# RSL10_Sch.net
KiCad netlist of a schematic drawn in Altium Designer
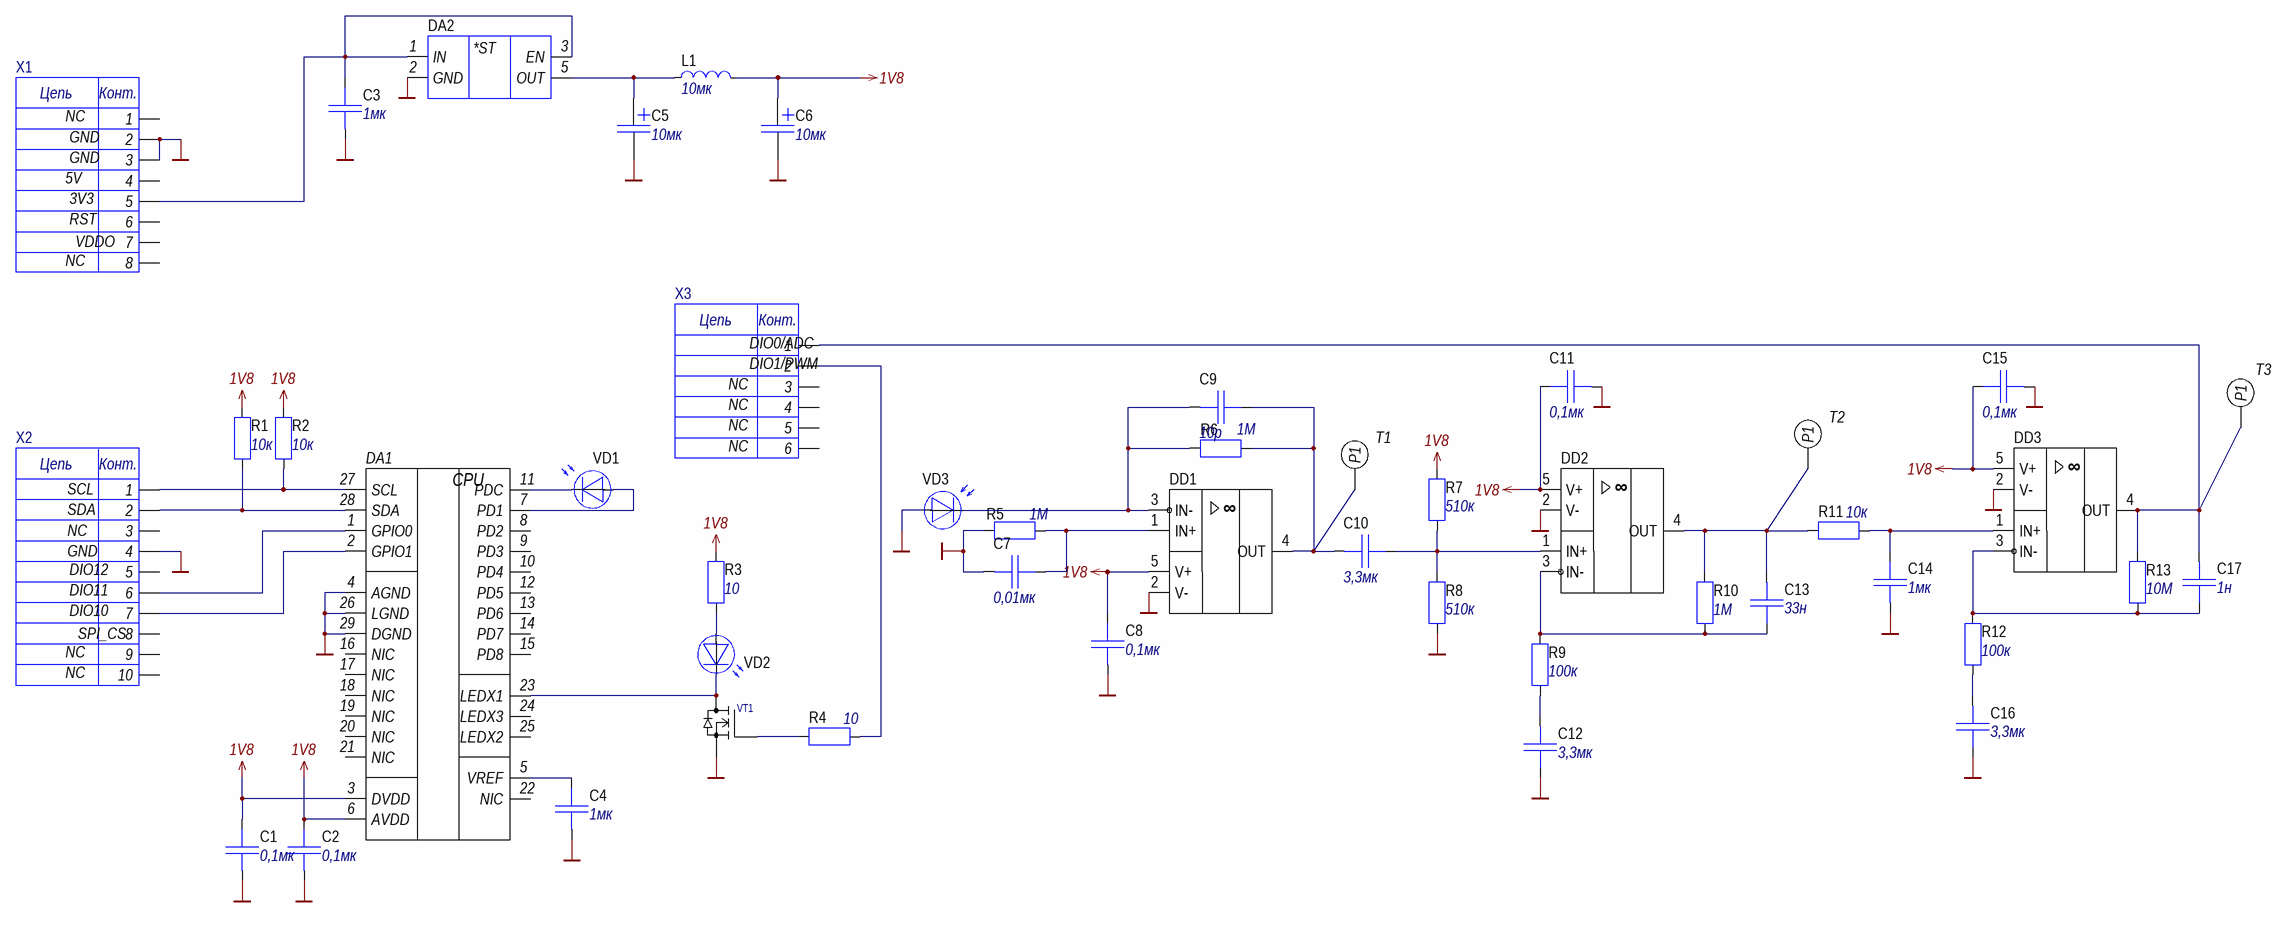
[diagram p0: RSL10_Sch.SchDoc]

(export (version "E")
  (design (tool "Eeschema 10.0.6"))
  (components
    (comp (ref "C1")
      (value "0,1мк")
      (footprint "cap0603")
      (description "Керамический конденсатор")
      (libsource (lib "RSL10_SchLib") (part "CapCer"))
    )
    (comp (ref "C2")
      (value "0,1мк")
      (footprint "cap0603")
      (description "Керамический конденсатор")
      (libsource (lib "RSL10_SchLib") (part "CapCer"))
    )
    (comp (ref "C3")
      (value "1мк")
      (footprint "cap0603")
      (description "Керамический конденсатор")
      (libsource (lib "RSL10_SchLib") (part "CapCer"))
    )
    (comp (ref "C4")
      (value "1мк")
      (footprint "cap0603")
      (description "Керамический конденсатор")
      (libsource (lib "RSL10_SchLib") (part "CapCer"))
    )
    (comp (ref "C5")
      (value "10мк")
      (description "Танталовый конденсатор")
      (libsource (lib "RSL10_SchLib") (part "CapTan"))
    )
    (comp (ref "C6")
      (value "10мк")
      (description "Танталовый конденсатор")
      (libsource (lib "RSL10_SchLib") (part "CapTan"))
    )
    (comp (ref "C7")
      (value "0,01мк")
      (footprint "cap0603")
      (description "Керамический конденсатор")
      (libsource (lib "RSL10_SchLib") (part "CapCer"))
    )
    (comp (ref "C8")
      (value "0,1мк")
      (footprint "cap0603")
      (description "Керамический конденсатор")
      (libsource (lib "RSL10_SchLib") (part "CapCer"))
    )
    (comp (ref "C9")
      (value "10p")
      (footprint "cap0603")
      (description "Керамический конденсатор")
      (libsource (lib "RSL10_SchLib") (part "CapCer"))
    )
    (comp (ref "C10")
      (value "3,3мк")
      (footprint "cap0603")
      (description "Керамический конденсатор")
      (libsource (lib "RSL10_SchLib") (part "CapCer"))
    )
    (comp (ref "C11")
      (value "0,1мк")
      (footprint "cap0603")
      (description "Керамический конденсатор")
      (libsource (lib "RSL10_SchLib") (part "CapCer"))
    )
    (comp (ref "C12")
      (value "3,3мк")
      (footprint "cap0603")
      (description "Керамический конденсатор")
      (libsource (lib "RSL10_SchLib") (part "CapCer"))
    )
    (comp (ref "C13")
      (value "33н")
      (footprint "cap0603")
      (description "Керамический конденсатор")
      (libsource (lib "RSL10_SchLib") (part "CapCer"))
    )
    (comp (ref "C14")
      (value "1мк")
      (footprint "cap0603")
      (description "Керамический конденсатор")
      (libsource (lib "RSL10_SchLib") (part "CapCer"))
    )
    (comp (ref "C15")
      (value "0,1мк")
      (footprint "cap0603")
      (description "Керамический конденсатор")
      (libsource (lib "RSL10_SchLib") (part "CapCer"))
    )
    (comp (ref "C16")
      (value "3,3мк")
      (footprint "cap0603")
      (description "Керамический конденсатор")
      (libsource (lib "RSL10_SchLib") (part "CapCer"))
    )
    (comp (ref "C17")
      (value "1н")
      (footprint "cap0603")
      (description "Керамический конденсатор")
      (libsource (lib "RSL10_SchLib") (part "CapCer"))
    )
    (comp (ref "DA1")
      (value "ADPD1080")
      (footprint "ADPD1080")
      (libsource (lib "RSL10_SchLib") (part "ADPD1080"))
    )
    (comp (ref "DA2")
      (value "TPS7A0218PDBVR")
      (footprint "TPS7A02")
      (libsource (lib "RSL10_SchLib") (part "LDO"))
    )
    (comp (ref "DD1")
      (value "operational amplifier_2")
      (footprint "OPA333")
      (description "Операционный усилитель")
      (libsource (lib "RSL10_SchLib") (part "operational amplifier_2"))
    )
    (comp (ref "DD2")
      (value "operational amplifier_1")
      (footprint "OPA333")
      (description "Операционный усилитель")
      (libsource (lib "RSL10_SchLib") (part "operational amplifier_1"))
    )
    (comp (ref "DD3")
      (value "operational amplifier_1")
      (footprint "OPA333")
      (description "Операционный усилитель")
      (libsource (lib "RSL10_SchLib") (part "operational amplifier_1"))
    )
    (comp (ref "L1")
      (value "10мк")
      (footprint "MLZ1608M100WT000")
      (description "Катушка индуктивности")
      (libsource (lib "RSL10_SchLib") (part "Ind"))
    )
    (comp (ref "R1")
      (value "10к")
      (footprint "Res0603")
      (description "Резистор")
      (fields (field (name "TOLERANCE") "5%") (field (name "MANUFACTURER") "АЛЯР.434110.005ТУ"))
      (libsource (lib "") (part "Res_1"))
    )
    (comp (ref "R2")
      (value "10к")
      (footprint "Res0603")
      (description "Резистор")
      (fields (field (name "TOLERANCE") "5%") (field (name "MANUFACTURER") "АЛЯР.434110.005ТУ"))
      (libsource (lib "") (part "Res_1"))
    )
    (comp (ref "R3")
      (value "10")
      (footprint "Res0603")
      (description "Резистор")
      (fields (field (name "TOLERANCE") "5%"))
      (libsource (lib "") (part "Res_2"))
    )
    (comp (ref "R4")
      (value "10")
      (footprint "Res0603")
      (description "Резистор")
      (fields (field (name "TOLERANCE") "5%"))
      (libsource (lib "") (part "Res_2"))
    )
    (comp (ref "R5")
      (value "1M")
      (footprint "Res0603")
      (description "Резистор")
      (fields (field (name "TOLERANCE") "1%"))
      (libsource (lib "RSL10_SchLib") (part "Res"))
    )
    (comp (ref "R6")
      (value "1M")
      (footprint "Res0603")
      (description "Резистор")
      (libsource (lib "RSL10_SchLib") (part "Res"))
    )
    (comp (ref "R7")
      (value "510к")
      (footprint "Res0603")
      (description "Резистор")
      (libsource (lib "") (part "Res_2"))
    )
    (comp (ref "R8")
      (value "510к")
      (footprint "Res0603")
      (description "Резистор")
      (libsource (lib "") (part "Res_2"))
    )
    (comp (ref "R9")
      (value "100к")
      (footprint "Res0603")
      (description "Резистор")
      (libsource (lib "") (part "Res_3"))
    )
    (comp (ref "R10")
      (value "1М")
      (footprint "Res0603")
      (description "Резистор")
      (fields (field (name "TOLERANCE") "1%"))
      (libsource (lib "") (part "Res_3"))
    )
    (comp (ref "R11")
      (value "10к")
      (footprint "Res0603")
      (description "Резистор")
      (fields (field (name "TOLERANCE") "5%") (field (name "MANUFACTURER") "АЛЯР.434110.005ТУ"))
      (libsource (lib "") (part "Res_3"))
    )
    (comp (ref "R12")
      (value "100к")
      (footprint "Res0603")
      (description "Резистор")
      (libsource (lib "") (part "Res_3"))
    )
    (comp (ref "R13")
      (value "10М")
      (footprint "Res0603")
      (description "Резистор")
      (libsource (lib "") (part "Res_3"))
    )
    (comp (ref "T1")
      (value "TestPoint")
      (footprint "TestPoint")
      (libsource (lib "RSL10_SchLib") (part "TestPoint"))
    )
    (comp (ref "T2")
      (value "TestPoint")
      (footprint "TestPoint")
      (libsource (lib "RSL10_SchLib") (part "TestPoint"))
    )
    (comp (ref "T3")
      (value "TestPoint")
      (footprint "TestPoint")
      (libsource (lib "RSL10_SchLib") (part "TestPoint"))
    )
    (comp (ref "VD1")
      (value "SFH 2703")
      (description "Photodiode")
      (libsource (lib "RSL10_SchLib") (part "Photodiode"))
    )
    (comp (ref "VD2")
      (value "15412094A9000аА0.339.189ТУ")
      (footprint "LED1206")
      (description "Излучатель")
      (libsource (lib "RSL10_SchLib") (part "Led"))
    )
    (comp (ref "VD3")
      (value "SFH 2703")
      (description "Photodiode")
      (libsource (lib "") (part "Photodiode_1"))
    )
    (comp (ref "VT1")
      (value "RU1J002YNTCL")
      (footprint "Mosfet")
      (description "N-MOSFET DirectFET SQ")
      (libsource (lib "RSL10_SchLib") (part "RU1J002YNTCL"))
    )
    (comp (ref "X1")
      (value "PLS-8БСАР.430420.014ТУ")
      (footprint "PSL_8")
      (libsource (lib "RSL10_SchLib") (part "PSL8"))
    )
    (comp (ref "X2")
      (value "PLS-10БСАР.430420.014ТУ")
      (footprint "PSL_10")
      (libsource (lib "RSL10_SchLib") (part "PSL10"))
    )
    (comp (ref "X3")
      (value "PLS-6БСАР.430420.014ТУ")
      (footprint "PSL_6")
      (libsource (lib "RSL10_SchLib") (part "PSL6"))
    )
  )
  (nets
    (net (code "1") (name "1V8") (class "Default")
      (node (ref "C1") (pin "2") (pinfunction "2_2") (pintype "passive"))
      (node (ref "C11") (pin "2") (pinfunction "2_2") (pintype "passive"))
      (node (ref "C15") (pin "2") (pinfunction "2_2") (pintype "passive"))
      (node (ref "C2") (pin "2") (pinfunction "2_2") (pintype "passive"))
      (node (ref "C6") (pin "1") (pinfunction "1_1") (pintype "passive"))
      (node (ref "C8") (pin "2") (pinfunction "2_2") (pintype "passive"))
      (node (ref "DA1") (pin "3") (pinfunction "DVDD_3") (pintype "passive"))
      (node (ref "DA1") (pin "6") (pinfunction "AVDD_6") (pintype "passive"))
      (node (ref "DD1") (pin "5") (pinfunction "V+_5") (pintype "passive"))
      (node (ref "DD2") (pin "5") (pinfunction "V+_5") (pintype "passive"))
      (node (ref "DD3") (pin "5") (pinfunction "V+_5") (pintype "passive"))
      (node (ref "L1") (pin "2") (pinfunction "2_2") (pintype "passive"))
      (node (ref "R1") (pin "1") (pinfunction "1_1") (pintype "passive"))
      (node (ref "R2") (pin "1") (pinfunction "1_1") (pintype "passive"))
      (node (ref "R3") (pin "2") (pinfunction "2_2") (pintype "passive"))
      (node (ref "R7") (pin "2") (pinfunction "2_2") (pintype "passive"))
    )
    (net (code "2") (name "GND") (class "Default")
      (node (ref "C1") (pin "1") (pinfunction "1_1") (pintype "passive"))
      (node (ref "C11") (pin "1") (pinfunction "1_1") (pintype "passive"))
      (node (ref "C12") (pin "2") (pinfunction "2_2") (pintype "passive"))
      (node (ref "C14") (pin "1") (pinfunction "1_1") (pintype "passive"))
      (node (ref "C15") (pin "1") (pinfunction "1_1") (pintype "passive"))
      (node (ref "C16") (pin "2") (pinfunction "2_2") (pintype "passive"))
      (node (ref "C2") (pin "1") (pinfunction "1_1") (pintype "passive"))
      (node (ref "C3") (pin "1") (pinfunction "1_1") (pintype "passive"))
      (node (ref "C4") (pin "1") (pinfunction "1_1") (pintype "passive"))
      (node (ref "C5") (pin "2") (pinfunction "2_2") (pintype "passive"))
      (node (ref "C6") (pin "2") (pinfunction "2_2") (pintype "passive"))
      (node (ref "C7") (pin "1") (pinfunction "1_1") (pintype "passive"))
      (node (ref "C8") (pin "1") (pinfunction "1_1") (pintype "passive"))
      (node (ref "DA1") (pin "26") (pinfunction "LGND_26") (pintype "passive"))
      (node (ref "DA1") (pin "29") (pinfunction "DGND_29") (pintype "passive"))
      (node (ref "DA1") (pin "4") (pinfunction "AGND_4") (pintype "passive"))
      (node (ref "DA2") (pin "2") (pinfunction "GND_2") (pintype "passive"))
      (node (ref "DD1") (pin "2") (pinfunction "V-_2") (pintype "passive"))
      (node (ref "DD2") (pin "2") (pinfunction "V-_2") (pintype "passive"))
      (node (ref "DD3") (pin "2") (pinfunction "V-_2") (pintype "passive"))
      (node (ref "R5") (pin "1") (pinfunction "1_1") (pintype "passive"))
      (node (ref "R8") (pin "1") (pinfunction "1_1") (pintype "passive"))
      (node (ref "VD3") (pin "1") (pinfunction "1_1") (pintype "passive"))
      (node (ref "VT1") (pin "2") (pinfunction "S_2") (pintype "power_in"))
      (node (ref "X1") (pin "2") (pinfunction "2_2") (pintype "passive"))
      (node (ref "X1") (pin "3") (pinfunction "3_3") (pintype "passive"))
      (node (ref "X2") (pin "4") (pinfunction "4_4") (pintype "passive"))
    )
    (net (code "3") (name "Net-(C12-Pad1)") (class "Default")
      (node (ref "C12") (pin "1") (pinfunction "1_1") (pintype "passive"))
      (node (ref "R9") (pin "2") (pinfunction "2_2") (pintype "passive"))
    )
    (net (code "4") (name "Net-(C16-Pad1)") (class "Default")
      (node (ref "C16") (pin "1") (pinfunction "1_1") (pintype "passive"))
      (node (ref "R12") (pin "2") (pinfunction "2_2") (pintype "passive"))
    )
    (net (code "5") (name "Net-(DA1-GPIO0)") (class "Default")
      (node (ref "DA1") (pin "1") (pinfunction "GPIO0_1") (pintype "passive"))
      (node (ref "X2") (pin "6") (pinfunction "6_6") (pintype "passive"))
    )
    (net (code "6") (name "Net-(DA1-GPIO1)") (class "Default")
      (node (ref "DA1") (pin "2") (pinfunction "GPIO1_2") (pintype "passive"))
      (node (ref "X2") (pin "7") (pinfunction "7_7") (pintype "passive"))
    )
    (net (code "7") (name "Net-(DA1-LEDX1)") (class "Default")
      (node (ref "DA1") (pin "23") (pinfunction "LEDX1_23") (pintype "passive"))
      (node (ref "VD2") (pin "K") (pinfunction "K_K") (pintype "passive"))
      (node (ref "VT1") (pin "3") (pinfunction "D_3") (pintype "power_in"))
    )
    (net (code "8") (name "Net-(DA1-PD1)") (class "Default")
      (node (ref "DA1") (pin "7") (pinfunction "PD1_7") (pintype "passive"))
      (node (ref "VD1") (pin "1") (pinfunction "1_1") (pintype "passive"))
    )
    (net (code "9") (name "Net-(DA1-PDC)") (class "Default")
      (node (ref "DA1") (pin "11") (pinfunction "PDC_11") (pintype "passive"))
      (node (ref "VD1") (pin "2") (pinfunction "2_2") (pintype "passive"))
    )
    (net (code "10") (name "Net-(DA1-SCL)") (class "Default")
      (node (ref "DA1") (pin "27") (pinfunction "SCL_27") (pintype "passive"))
      (node (ref "R2") (pin "2") (pinfunction "2_2") (pintype "passive"))
      (node (ref "X2") (pin "1") (pinfunction "1_1") (pintype "passive"))
    )
    (net (code "11") (name "Net-(DA1-SDA)") (class "Default")
      (node (ref "DA1") (pin "28") (pinfunction "SDA_28") (pintype "passive"))
      (node (ref "R1") (pin "2") (pinfunction "2_2") (pintype "passive"))
      (node (ref "X2") (pin "2") (pinfunction "2_2") (pintype "passive"))
    )
    (net (code "12") (name "Net-(DA1-VREF)") (class "Default")
      (node (ref "C4") (pin "2") (pinfunction "2_2") (pintype "passive"))
      (node (ref "DA1") (pin "5") (pinfunction "VREF_5") (pintype "passive"))
    )
    (net (code "13") (name "Net-(DA2-EN)") (class "Default")
      (node (ref "C3") (pin "2") (pinfunction "2_2") (pintype "passive"))
      (node (ref "DA2") (pin "1") (pinfunction "IN_1") (pintype "passive"))
      (node (ref "DA2") (pin "3") (pinfunction "EN_3") (pintype "passive"))
      (node (ref "X1") (pin "5") (pinfunction "5_5") (pintype "passive"))
    )
    (net (code "14") (name "Net-(DA2-OUT)") (class "Default")
      (node (ref "C5") (pin "1") (pinfunction "1_1") (pintype "passive"))
      (node (ref "DA2") (pin "5") (pinfunction "OUT_5") (pintype "passive"))
      (node (ref "L1") (pin "1") (pinfunction "1_1") (pintype "passive"))
    )
    (net (code "15") (name "Net-(DD1-IN+)") (class "Default")
      (node (ref "C7") (pin "2") (pinfunction "2_2") (pintype "passive"))
      (node (ref "DD1") (pin "1") (pinfunction "IN+_1") (pintype "passive"))
      (node (ref "R5") (pin "2") (pinfunction "2_2") (pintype "passive"))
    )
    (net (code "16") (name "Net-(DD1-IN-)") (class "Default")
      (node (ref "C9") (pin "1") (pinfunction "1_1") (pintype "passive"))
      (node (ref "DD1") (pin "3") (pinfunction "IN-_3") (pintype "passive"))
      (node (ref "R6") (pin "1") (pinfunction "1_1") (pintype "passive"))
      (node (ref "VD3") (pin "2") (pinfunction "2_2") (pintype "passive"))
    )
    (net (code "17") (name "Net-(DD1-OUT)") (class "Default")
      (node (ref "C10") (pin "1") (pinfunction "1_1") (pintype "passive"))
      (node (ref "C9") (pin "2") (pinfunction "2_2") (pintype "passive"))
      (node (ref "DD1") (pin "4") (pinfunction "OUT_4") (pintype "passive"))
      (node (ref "R6") (pin "2") (pinfunction "2_2") (pintype "passive"))
      (node (ref "T1") (pin "T") (pinfunction "P1_T") (pintype "passive"))
    )
    (net (code "18") (name "Net-(DD2-IN+)") (class "Default")
      (node (ref "C10") (pin "2") (pinfunction "2_2") (pintype "passive"))
      (node (ref "DD2") (pin "1") (pinfunction "IN+_1") (pintype "passive"))
      (node (ref "R7") (pin "1") (pinfunction "1_1") (pintype "passive"))
      (node (ref "R8") (pin "2") (pinfunction "2_2") (pintype "passive"))
    )
    (net (code "19") (name "Net-(DD2-IN-)") (class "Default")
      (node (ref "C13") (pin "2") (pinfunction "2_2") (pintype "passive"))
      (node (ref "DD2") (pin "3") (pinfunction "IN-_3") (pintype "passive"))
      (node (ref "R10") (pin "2") (pinfunction "2_2") (pintype "passive"))
      (node (ref "R9") (pin "1") (pinfunction "1_1") (pintype "passive"))
    )
    (net (code "20") (name "Net-(DD2-OUT)") (class "Default")
      (node (ref "C13") (pin "1") (pinfunction "1_1") (pintype "passive"))
      (node (ref "DD2") (pin "4") (pinfunction "OUT_4") (pintype "passive"))
      (node (ref "R10") (pin "1") (pinfunction "1_1") (pintype "passive"))
      (node (ref "R11") (pin "2") (pinfunction "2_2") (pintype "passive"))
      (node (ref "T2") (pin "T") (pinfunction "P1_T") (pintype "passive"))
    )
    (net (code "21") (name "Net-(DD3-IN+)") (class "Default")
      (node (ref "C14") (pin "2") (pinfunction "2_2") (pintype "passive"))
      (node (ref "DD3") (pin "1") (pinfunction "IN+_1") (pintype "passive"))
      (node (ref "R11") (pin "1") (pinfunction "1_1") (pintype "passive"))
    )
    (net (code "22") (name "Net-(DD3-IN-)") (class "Default")
      (node (ref "C17") (pin "2") (pinfunction "2_2") (pintype "passive"))
      (node (ref "DD3") (pin "3") (pinfunction "IN-_3") (pintype "passive"))
      (node (ref "R12") (pin "1") (pinfunction "1_1") (pintype "passive"))
      (node (ref "R13") (pin "2") (pinfunction "2_2") (pintype "passive"))
    )
    (net (code "23") (name "Net-(DD3-OUT)") (class "Default")
      (node (ref "C17") (pin "1") (pinfunction "1_1") (pintype "passive"))
      (node (ref "DD3") (pin "4") (pinfunction "OUT_4") (pintype "passive"))
      (node (ref "R13") (pin "1") (pinfunction "1_1") (pintype "passive"))
      (node (ref "T3") (pin "T") (pinfunction "P1_T") (pintype "passive"))
      (node (ref "X3") (pin "1") (pinfunction "1_1") (pintype "passive"))
    )
    (net (code "24") (name "Net-(R3-Pad1)") (class "Default")
      (node (ref "R3") (pin "1") (pinfunction "1_1") (pintype "passive"))
      (node (ref "VD2") (pin "A") (pinfunction "A_A") (pintype "passive"))
    )
    (net (code "25") (name "Net-(R4-Pad2)") (class "Default")
      (node (ref "R4") (pin "2") (pinfunction "2_2") (pintype "passive"))
      (node (ref "X3") (pin "2") (pinfunction "2_2") (pintype "passive"))
    )
    (net (code "26") (name "Net-(VT1-G)") (class "Default")
      (node (ref "R4") (pin "1") (pinfunction "1_1") (pintype "passive"))
      (node (ref "VT1") (pin "1") (pinfunction "G_1") (pintype "power_in"))
    )
    (net (code "27") (name "unconnected-(DA1-LEDX2-Pad25)") (class "Default")
      (node (ref "DA1") (pin "25") (pinfunction "LEDX2_25") (pintype "passive"))
    )
    (net (code "28") (name "unconnected-(DA1-LEDX3-Pad24)") (class "Default")
      (node (ref "DA1") (pin "24") (pinfunction "LEDX3_24") (pintype "passive"))
    )
    (net (code "29") (name "unconnected-(DA1-NIC-Pad16)") (class "Default")
      (node (ref "DA1") (pin "16") (pinfunction "NIC_16") (pintype "passive"))
    )
    (net (code "30") (name "unconnected-(DA1-NIC-Pad17)") (class "Default")
      (node (ref "DA1") (pin "17") (pinfunction "NIC_17") (pintype "passive"))
    )
    (net (code "31") (name "unconnected-(DA1-NIC-Pad18)") (class "Default")
      (node (ref "DA1") (pin "18") (pinfunction "NIC_18") (pintype "passive"))
    )
    (net (code "32") (name "unconnected-(DA1-NIC-Pad19)") (class "Default")
      (node (ref "DA1") (pin "19") (pinfunction "NIC_19") (pintype "passive"))
    )
    (net (code "33") (name "unconnected-(DA1-NIC-Pad20)") (class "Default")
      (node (ref "DA1") (pin "20") (pinfunction "NIC_20") (pintype "passive"))
    )
    (net (code "34") (name "unconnected-(DA1-NIC-Pad21)") (class "Default")
      (node (ref "DA1") (pin "21") (pinfunction "NIC_21") (pintype "passive"))
    )
    (net (code "35") (name "unconnected-(DA1-NIC-Pad22)") (class "Default")
      (node (ref "DA1") (pin "22") (pinfunction "NIC_22") (pintype "passive"))
    )
    (net (code "36") (name "unconnected-(DA1-PD2-Pad8)") (class "Default")
      (node (ref "DA1") (pin "8") (pinfunction "PD2_8") (pintype "passive"))
    )
    (net (code "37") (name "unconnected-(DA1-PD3-Pad9)") (class "Default")
      (node (ref "DA1") (pin "9") (pinfunction "PD3_9") (pintype "passive"))
    )
    (net (code "38") (name "unconnected-(DA1-PD4-Pad10)") (class "Default")
      (node (ref "DA1") (pin "10") (pinfunction "PD4_10") (pintype "passive"))
    )
    (net (code "39") (name "unconnected-(DA1-PD5-Pad12)") (class "Default")
      (node (ref "DA1") (pin "12") (pinfunction "PD5_12") (pintype "passive"))
    )
    (net (code "40") (name "unconnected-(DA1-PD6-Pad13)") (class "Default")
      (node (ref "DA1") (pin "13") (pinfunction "PD6_13") (pintype "passive"))
    )
    (net (code "41") (name "unconnected-(DA1-PD7-Pad14)") (class "Default")
      (node (ref "DA1") (pin "14") (pinfunction "PD7_14") (pintype "passive"))
    )
    (net (code "42") (name "unconnected-(DA1-PD8-Pad15)") (class "Default")
      (node (ref "DA1") (pin "15") (pinfunction "PD8_15") (pintype "passive"))
    )
    (net (code "43") (name "unconnected-(X1-Pad1)") (class "Default")
      (node (ref "X1") (pin "1") (pinfunction "1_1") (pintype "passive"))
    )
    (net (code "44") (name "unconnected-(X1-Pad4)") (class "Default")
      (node (ref "X1") (pin "4") (pinfunction "4_4") (pintype "passive"))
    )
    (net (code "45") (name "unconnected-(X1-Pad6)") (class "Default")
      (node (ref "X1") (pin "6") (pinfunction "6_6") (pintype "passive"))
    )
    (net (code "46") (name "unconnected-(X1-Pad7)") (class "Default")
      (node (ref "X1") (pin "7") (pinfunction "7_7") (pintype "passive"))
    )
    (net (code "47") (name "unconnected-(X1-Pad8)") (class "Default")
      (node (ref "X1") (pin "8") (pinfunction "8_8") (pintype "passive"))
    )
    (net (code "48") (name "unconnected-(X2-Pad3)") (class "Default")
      (node (ref "X2") (pin "3") (pinfunction "3_3") (pintype "passive"))
    )
    (net (code "49") (name "unconnected-(X2-Pad5)") (class "Default")
      (node (ref "X2") (pin "5") (pinfunction "5_5") (pintype "passive"))
    )
    (net (code "50") (name "unconnected-(X2-Pad8)") (class "Default")
      (node (ref "X2") (pin "8") (pinfunction "8_8") (pintype "passive"))
    )
    (net (code "51") (name "unconnected-(X2-Pad9)") (class "Default")
      (node (ref "X2") (pin "9") (pinfunction "9_9") (pintype "passive"))
    )
    (net (code "52") (name "unconnected-(X2-Pad10)") (class "Default")
      (node (ref "X2") (pin "10") (pinfunction "10_10") (pintype "passive"))
    )
    (net (code "53") (name "unconnected-(X3-Pad3)") (class "Default")
      (node (ref "X3") (pin "3") (pinfunction "3_3") (pintype "passive"))
    )
    (net (code "54") (name "unconnected-(X3-Pad4)") (class "Default")
      (node (ref "X3") (pin "4") (pinfunction "4_4") (pintype "passive"))
    )
    (net (code "55") (name "unconnected-(X3-Pad5)") (class "Default")
      (node (ref "X3") (pin "5") (pinfunction "5_5") (pintype "passive"))
    )
    (net (code "56") (name "unconnected-(X3-Pad6)") (class "Default")
      (node (ref "X3") (pin "6") (pinfunction "6_6") (pintype "passive"))
    )
  )
)
